# FTDI.net
KiCad netlist of a schematic drawn in Altium Designer
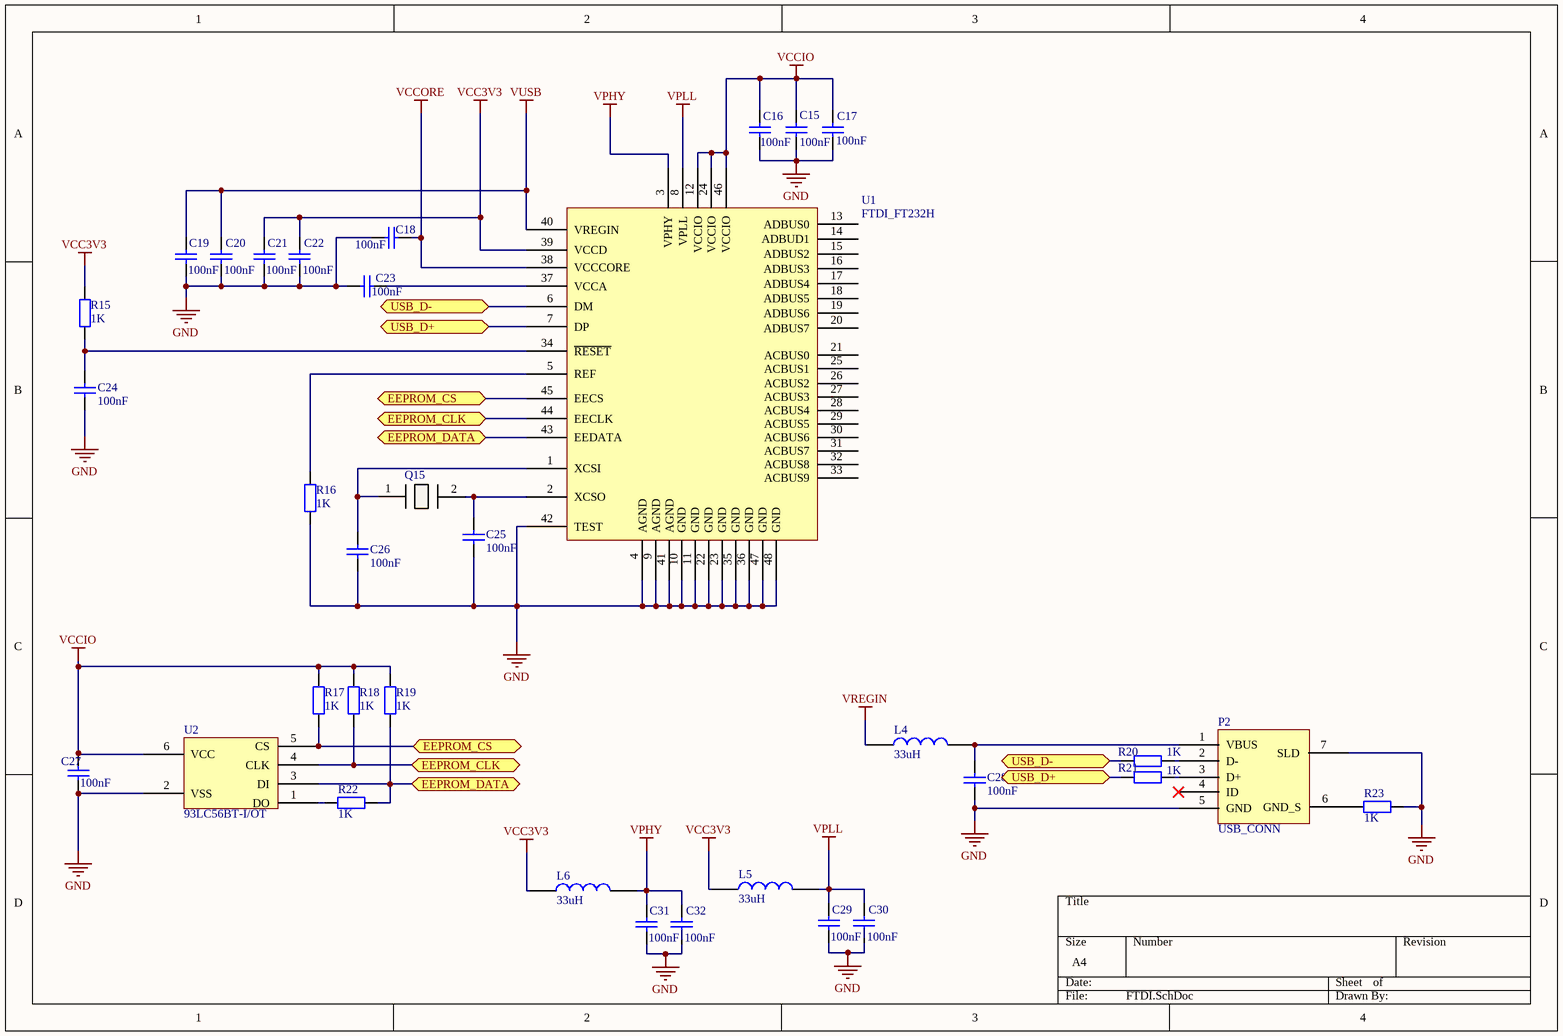
[diagram p0: FTDI.SchDoc]

(export (version "E")
  (design (tool "Eeschema 10.0.6"))
  (components
    (comp (ref "C15")
      (value "100nF")
      (footprint "AXIAL-0.3")
      (description "Capacitor")
      (libsource (lib "hallglib") (part "CAP"))
    )
    (comp (ref "C16")
      (value "100nF")
      (footprint "AXIAL-0.3")
      (description "Capacitor")
      (libsource (lib "hallglib") (part "CAP"))
    )
    (comp (ref "C17")
      (value "100nF")
      (footprint "AXIAL-0.3")
      (description "Capacitor")
      (libsource (lib "hallglib") (part "CAP"))
    )
    (comp (ref "C18")
      (value "100nF")
      (footprint "AXIAL-0.3")
      (description "Capacitor")
      (libsource (lib "hallglib") (part "CAP"))
    )
    (comp (ref "C19")
      (value "100nF")
      (footprint "AXIAL-0.3")
      (description "Capacitor")
      (libsource (lib "hallglib") (part "CAP"))
    )
    (comp (ref "C20")
      (value "100nF")
      (footprint "AXIAL-0.3")
      (description "Capacitor")
      (libsource (lib "hallglib") (part "CAP"))
    )
    (comp (ref "C21")
      (value "100nF")
      (footprint "AXIAL-0.3")
      (description "Capacitor")
      (libsource (lib "hallglib") (part "CAP"))
    )
    (comp (ref "C22")
      (value "100nF")
      (footprint "AXIAL-0.3")
      (description "Capacitor")
      (libsource (lib "hallglib") (part "CAP"))
    )
    (comp (ref "C23")
      (value "100nF")
      (footprint "AXIAL-0.3")
      (description "Capacitor")
      (libsource (lib "hallglib") (part "CAP"))
    )
    (comp (ref "C24")
      (value "100nF")
      (footprint "AXIAL-0.3")
      (description "Capacitor")
      (libsource (lib "hallglib") (part "CAP"))
    )
    (comp (ref "C25")
      (value "100nF")
      (footprint "AXIAL-0.3")
      (description "Capacitor")
      (libsource (lib "hallglib") (part "CAP"))
    )
    (comp (ref "C26")
      (value "100nF")
      (footprint "AXIAL-0.3")
      (description "Capacitor")
      (libsource (lib "hallglib") (part "CAP"))
    )
    (comp (ref "C27")
      (value "100nF")
      (footprint "AXIAL-0.3")
      (description "Capacitor")
      (libsource (lib "hallglib") (part "CAP"))
    )
    (comp (ref "C28")
      (value "100nF")
      (footprint "AXIAL-0.3")
      (description "Capacitor")
      (libsource (lib "hallglib") (part "CAP"))
    )
    (comp (ref "C29")
      (value "100nF")
      (footprint "AXIAL-0.3")
      (description "Capacitor")
      (libsource (lib "hallglib") (part "CAP"))
    )
    (comp (ref "C30")
      (value "100nF")
      (footprint "AXIAL-0.3")
      (description "Capacitor")
      (libsource (lib "hallglib") (part "CAP"))
    )
    (comp (ref "C31")
      (value "100nF")
      (footprint "AXIAL-0.3")
      (description "Capacitor")
      (libsource (lib "hallglib") (part "CAP"))
    )
    (comp (ref "C32")
      (value "100nF")
      (footprint "AXIAL-0.3")
      (description "Capacitor")
      (libsource (lib "hallglib") (part "CAP"))
    )
    (comp (ref "L4")
      (value "33uH")
      (footprint "AXIAL-0.3")
      (description "Inductor")
      (libsource (lib "hallglib") (part "IND"))
    )
    (comp (ref "L5")
      (value "33uH")
      (footprint "AXIAL-0.3")
      (description "Inductor")
      (libsource (lib "hallglib") (part "IND"))
    )
    (comp (ref "L6")
      (value "33uH")
      (footprint "AXIAL-0.3")
      (description "Inductor")
      (libsource (lib "hallglib") (part "IND"))
    )
    (comp (ref "P2")
      (value "USB_CONN")
      (footprint "SMD_Micro_USB")
      (description "usb, smd csatlakozó")
      (libsource (lib "hallglib") (part "USB_connector"))
    )
    (comp (ref "Q15")
      (value "HC49/4HSMX")
      (footprint "Crystal_10MHz")
      (description "kristály")
      (libsource (lib "hallglib") (part "HC49/4HSMX"))
    )
    (comp (ref "R15")
      (value "1K")
      (footprint "AXIAL-0.3")
      (description "Resistor")
      (libsource (lib "hallglib") (part "RES"))
    )
    (comp (ref "R16")
      (value "1K")
      (footprint "AXIAL-0.3")
      (description "Resistor")
      (libsource (lib "") (part "RES_1"))
    )
    (comp (ref "R17")
      (value "1K")
      (footprint "AXIAL-0.3")
      (description "Resistor")
      (libsource (lib "") (part "RES_1"))
    )
    (comp (ref "R18")
      (value "1K")
      (footprint "AXIAL-0.3")
      (description "Resistor")
      (libsource (lib "") (part "RES_1"))
    )
    (comp (ref "R19")
      (value "1K")
      (footprint "AXIAL-0.3")
      (description "Resistor")
      (libsource (lib "") (part "RES_1"))
    )
    (comp (ref "R20")
      (value "1K")
      (footprint "AXIAL-0.3")
      (description "Resistor")
      (libsource (lib "hallglib") (part "RES"))
    )
    (comp (ref "R21")
      (value "1K")
      (footprint "AXIAL-0.3")
      (description "Resistor")
      (libsource (lib "hallglib") (part "RES"))
    )
    (comp (ref "R22")
      (value "1K")
      (footprint "AXIAL-0.3")
      (description "Resistor")
      (libsource (lib "hallglib") (part "RES"))
    )
    (comp (ref "R23")
      (value "1K")
      (footprint "AXIAL-0.3")
      (description "Resistor")
      (libsource (lib "hallglib") (part "RES"))
    )
    (comp (ref "U1")
      (value "FTDI_FT232H")
      (footprint "LQFP48")
      (description "USB transciever")
      (libsource (lib "hallglib") (part "FTDI_FT232H"))
    )
    (comp (ref "U2")
      (value "93LC56BT-I/OT")
      (footprint "SOT-23")
      (description "EEPROM")
      (libsource (lib "hallglib") (part "93LC56BT-I/OT"))
    )
  )
  (nets
    (net (code "1") (name "/EEPROM_CLK") (class "Default")
      (node (ref "R18") (pin "1") (pinfunction "1_1") (pintype "passive"))
      (node (ref "U1") (pin "44") (pinfunction "EECLK_44") (pintype "passive"))
      (node (ref "U2") (pin "4") (pinfunction "CLK_4") (pintype "passive"))
    )
    (net (code "2") (name "/EEPROM_CS") (class "Default")
      (node (ref "R17") (pin "1") (pinfunction "1_1") (pintype "passive"))
      (node (ref "U1") (pin "45") (pinfunction "EECS_45") (pintype "passive"))
      (node (ref "U2") (pin "5") (pinfunction "CS_5") (pintype "passive"))
    )
    (net (code "3") (name "/EEPROM_DATA") (class "Default")
      (node (ref "R19") (pin "1") (pinfunction "1_1") (pintype "passive"))
      (node (ref "R22") (pin "2") (pinfunction "2_2") (pintype "passive"))
      (node (ref "U1") (pin "43") (pinfunction "EEDATA_43") (pintype "passive"))
      (node (ref "U2") (pin "3") (pinfunction "DI_3") (pintype "passive"))
    )
    (net (code "4") (name "/USB_D+") (class "Default")
      (node (ref "R21") (pin "1") (pinfunction "1_1") (pintype "passive"))
      (node (ref "U1") (pin "7") (pinfunction "DP_7") (pintype "passive"))
    )
    (net (code "5") (name "/USB_D-") (class "Default")
      (node (ref "R20") (pin "1") (pinfunction "1_1") (pintype "passive"))
      (node (ref "U1") (pin "6") (pinfunction "DM_6") (pintype "passive"))
    )
    (net (code "6") (name "GND") (class "Default")
      (node (ref "C15") (pin "1") (pinfunction "1_1") (pintype "passive"))
      (node (ref "C16") (pin "1") (pinfunction "1_1") (pintype "passive"))
      (node (ref "C17") (pin "1") (pinfunction "1_1") (pintype "passive"))
      (node (ref "C18") (pin "1") (pinfunction "1_1") (pintype "passive"))
      (node (ref "C19") (pin "1") (pinfunction "1_1") (pintype "passive"))
      (node (ref "C20") (pin "1") (pinfunction "1_1") (pintype "passive"))
      (node (ref "C21") (pin "1") (pinfunction "1_1") (pintype "passive"))
      (node (ref "C22") (pin "1") (pinfunction "1_1") (pintype "passive"))
      (node (ref "C23") (pin "2") (pinfunction "2_2") (pintype "passive"))
      (node (ref "C24") (pin "1") (pinfunction "1_1") (pintype "passive"))
      (node (ref "C25") (pin "1") (pinfunction "1_1") (pintype "passive"))
      (node (ref "C26") (pin "1") (pinfunction "1_1") (pintype "passive"))
      (node (ref "C27") (pin "1") (pinfunction "1_1") (pintype "passive"))
      (node (ref "C28") (pin "1") (pinfunction "1_1") (pintype "passive"))
      (node (ref "C29") (pin "1") (pinfunction "1_1") (pintype "passive"))
      (node (ref "C30") (pin "1") (pinfunction "1_1") (pintype "passive"))
      (node (ref "C31") (pin "1") (pinfunction "1_1") (pintype "passive"))
      (node (ref "C32") (pin "1") (pinfunction "1_1") (pintype "passive"))
      (node (ref "P2") (pin "5") (pinfunction "GND_5") (pintype "passive"))
      (node (ref "P2") (pin "7") (pinfunction "SLD_7") (pintype "passive"))
      (node (ref "R16") (pin "1") (pinfunction "1_1") (pintype "passive"))
      (node (ref "R23") (pin "2") (pinfunction "2_2") (pintype "passive"))
      (node (ref "U1") (pin "10") (pinfunction "GND_10") (pintype "passive"))
      (node (ref "U1") (pin "11") (pinfunction "GND_11") (pintype "passive"))
      (node (ref "U1") (pin "22") (pinfunction "GND_22") (pintype "passive"))
      (node (ref "U1") (pin "23") (pinfunction "GND_23") (pintype "passive"))
      (node (ref "U1") (pin "35") (pinfunction "GND_35") (pintype "passive"))
      (node (ref "U1") (pin "36") (pinfunction "GND_36") (pintype "passive"))
      (node (ref "U1") (pin "4") (pinfunction "AGND_4") (pintype "passive"))
      (node (ref "U1") (pin "41") (pinfunction "AGND_41") (pintype "passive"))
      (node (ref "U1") (pin "42") (pinfunction "TEST_42") (pintype "passive"))
      (node (ref "U1") (pin "47") (pinfunction "GND_47") (pintype "passive"))
      (node (ref "U1") (pin "48") (pinfunction "GND_48") (pintype "passive"))
      (node (ref "U1") (pin "9") (pinfunction "AGND_9") (pintype "passive"))
      (node (ref "U2") (pin "2") (pinfunction "VSS_2") (pintype "passive"))
    )
    (net (code "7") (name "Net-(P2-D+)") (class "Default")
      (node (ref "P2") (pin "3") (pinfunction "D+_3") (pintype "passive"))
      (node (ref "R21") (pin "2") (pinfunction "2_2") (pintype "passive"))
    )
    (net (code "8") (name "Net-(P2-D-)") (class "Default")
      (node (ref "P2") (pin "2") (pinfunction "D-_2") (pintype "passive"))
      (node (ref "R20") (pin "2") (pinfunction "2_2") (pintype "passive"))
    )
    (net (code "9") (name "Net-(P2-GND_S)") (class "Default")
      (node (ref "P2") (pin "6") (pinfunction "GND_S_6") (pintype "passive"))
      (node (ref "R23") (pin "1") (pinfunction "1_1") (pintype "passive"))
    )
    (net (code "10") (name "Net-(P2-VBUS)") (class "Default")
      (node (ref "C28") (pin "2") (pinfunction "2_2") (pintype "passive"))
      (node (ref "L4") (pin "2") (pinfunction "2_2") (pintype "passive"))
      (node (ref "P2") (pin "1") (pinfunction "VBUS_1") (pintype "passive"))
    )
    (net (code "11") (name "Net-(Q15-X1)") (class "Default")
      (node (ref "C26") (pin "2") (pinfunction "2_2") (pintype "passive"))
      (node (ref "Q15") (pin "1") (pinfunction "X1_1") (pintype "passive"))
      (node (ref "U1") (pin "1") (pinfunction "XCSI_1") (pintype "passive"))
    )
    (net (code "12") (name "Net-(Q15-X2)") (class "Default")
      (node (ref "C25") (pin "2") (pinfunction "2_2") (pintype "passive"))
      (node (ref "Q15") (pin "2") (pinfunction "X2_2") (pintype "passive"))
      (node (ref "U1") (pin "2") (pinfunction "XCSO_2") (pintype "passive"))
    )
    (net (code "13") (name "Net-(U1-REF)") (class "Default")
      (node (ref "R16") (pin "2") (pinfunction "2_2") (pintype "passive"))
      (node (ref "U1") (pin "5") (pinfunction "REF_5") (pintype "passive"))
    )
    (net (code "14") (name "Net-(U1-VCCA)") (class "Default")
      (node (ref "C23") (pin "1") (pinfunction "1_1") (pintype "passive"))
      (node (ref "U1") (pin "37") (pinfunction "VCCA_37") (pintype "passive"))
    )
    (net (code "15") (name "Net-(U1-~{RESET})") (class "Default")
      (node (ref "C24") (pin "2") (pinfunction "2_2") (pintype "passive"))
      (node (ref "R15") (pin "1") (pinfunction "1_1") (pintype "passive"))
      (node (ref "U1") (pin "34") (pinfunction "~{RESET}_34") (pintype "passive"))
    )
    (net (code "16") (name "Net-(U2-DO)") (class "Default")
      (node (ref "R22") (pin "1") (pinfunction "1_1") (pintype "passive"))
      (node (ref "U2") (pin "1") (pinfunction "DO_1") (pintype "passive"))
    )
    (net (code "17") (name "VCC3V3") (class "Default")
      (node (ref "C21") (pin "2") (pinfunction "2_2") (pintype "passive"))
      (node (ref "C22") (pin "2") (pinfunction "2_2") (pintype "passive"))
      (node (ref "L5") (pin "1") (pinfunction "1_1") (pintype "passive"))
      (node (ref "L6") (pin "1") (pinfunction "1_1") (pintype "passive"))
      (node (ref "R15") (pin "2") (pinfunction "2_2") (pintype "passive"))
      (node (ref "U1") (pin "39") (pinfunction "VCCD_39") (pintype "passive"))
    )
    (net (code "18") (name "VCCIO") (class "Default")
      (node (ref "C15") (pin "2") (pinfunction "2_2") (pintype "passive"))
      (node (ref "C16") (pin "2") (pinfunction "2_2") (pintype "passive"))
      (node (ref "C17") (pin "2") (pinfunction "2_2") (pintype "passive"))
      (node (ref "C27") (pin "2") (pinfunction "2_2") (pintype "passive"))
      (node (ref "R17") (pin "2") (pinfunction "2_2") (pintype "passive"))
      (node (ref "R18") (pin "2") (pinfunction "2_2") (pintype "passive"))
      (node (ref "R19") (pin "2") (pinfunction "2_2") (pintype "passive"))
      (node (ref "U1") (pin "12") (pinfunction "VCCIO_12") (pintype "passive"))
      (node (ref "U1") (pin "24") (pinfunction "VCCIO_24") (pintype "passive"))
      (node (ref "U1") (pin "46") (pinfunction "VCCIO_46") (pintype "passive"))
      (node (ref "U2") (pin "6") (pinfunction "VCC_6") (pintype "passive"))
    )
    (net (code "19") (name "VCCORE") (class "Default")
      (node (ref "C18") (pin "2") (pinfunction "2_2") (pintype "passive"))
      (node (ref "U1") (pin "38") (pinfunction "VCCCORE_38") (pintype "passive"))
    )
    (net (code "20") (name "VPHY") (class "Default")
      (node (ref "C31") (pin "2") (pinfunction "2_2") (pintype "passive"))
      (node (ref "C32") (pin "2") (pinfunction "2_2") (pintype "passive"))
      (node (ref "L6") (pin "2") (pinfunction "2_2") (pintype "passive"))
      (node (ref "U1") (pin "3") (pinfunction "VPHY_3") (pintype "passive"))
    )
    (net (code "21") (name "VPLL") (class "Default")
      (node (ref "C29") (pin "2") (pinfunction "2_2") (pintype "passive"))
      (node (ref "C30") (pin "2") (pinfunction "2_2") (pintype "passive"))
      (node (ref "L5") (pin "2") (pinfunction "2_2") (pintype "passive"))
      (node (ref "U1") (pin "8") (pinfunction "VPLL_8") (pintype "passive"))
    )
    (net (code "22") (name "VREGIN") (class "Default")
      (node (ref "L4") (pin "1") (pinfunction "1_1") (pintype "passive"))
    )
    (net (code "23") (name "VUSB") (class "Default")
      (node (ref "C19") (pin "2") (pinfunction "2_2") (pintype "passive"))
      (node (ref "C20") (pin "2") (pinfunction "2_2") (pintype "passive"))
      (node (ref "U1") (pin "40") (pinfunction "VREGIN_40") (pintype "passive"))
    )
    (net (code "24") (name "unconnected-(P2-ID-Pad4)") (class "Default")
      (node (ref "P2") (pin "4") (pinfunction "ID_4") (pintype "passive+no_connect"))
    )
    (net (code "25") (name "unconnected-(U1-ACBUS0-Pad21)") (class "Default")
      (node (ref "U1") (pin "21") (pinfunction "ACBUS0_21") (pintype "passive"))
    )
    (net (code "26") (name "unconnected-(U1-ACBUS1-Pad25)") (class "Default")
      (node (ref "U1") (pin "25") (pinfunction "ACBUS1_25") (pintype "passive"))
    )
    (net (code "27") (name "unconnected-(U1-ACBUS2-Pad26)") (class "Default")
      (node (ref "U1") (pin "26") (pinfunction "ACBUS2_26") (pintype "passive"))
    )
    (net (code "28") (name "unconnected-(U1-ACBUS3-Pad27)") (class "Default")
      (node (ref "U1") (pin "27") (pinfunction "ACBUS3_27") (pintype "passive"))
    )
    (net (code "29") (name "unconnected-(U1-ACBUS4-Pad28)") (class "Default")
      (node (ref "U1") (pin "28") (pinfunction "ACBUS4_28") (pintype "passive"))
    )
    (net (code "30") (name "unconnected-(U1-ACBUS5-Pad29)") (class "Default")
      (node (ref "U1") (pin "29") (pinfunction "ACBUS5_29") (pintype "passive"))
    )
    (net (code "31") (name "unconnected-(U1-ACBUS6-Pad30)") (class "Default")
      (node (ref "U1") (pin "30") (pinfunction "ACBUS6_30") (pintype "passive"))
    )
    (net (code "32") (name "unconnected-(U1-ACBUS7-Pad31)") (class "Default")
      (node (ref "U1") (pin "31") (pinfunction "ACBUS7_31") (pintype "passive"))
    )
    (net (code "33") (name "unconnected-(U1-ACBUS8-Pad32)") (class "Default")
      (node (ref "U1") (pin "32") (pinfunction "ACBUS8_32") (pintype "passive"))
    )
    (net (code "34") (name "unconnected-(U1-ACBUS9-Pad33)") (class "Default")
      (node (ref "U1") (pin "33") (pinfunction "ACBUS9_33") (pintype "passive"))
    )
    (net (code "35") (name "unconnected-(U1-ADBUD1-Pad14)") (class "Default")
      (node (ref "U1") (pin "14") (pinfunction "ADBUD1_14") (pintype "passive"))
    )
    (net (code "36") (name "unconnected-(U1-ADBUS0-Pad13)") (class "Default")
      (node (ref "U1") (pin "13") (pinfunction "ADBUS0_13") (pintype "passive"))
    )
    (net (code "37") (name "unconnected-(U1-ADBUS2-Pad15)") (class "Default")
      (node (ref "U1") (pin "15") (pinfunction "ADBUS2_15") (pintype "passive"))
    )
    (net (code "38") (name "unconnected-(U1-ADBUS3-Pad16)") (class "Default")
      (node (ref "U1") (pin "16") (pinfunction "ADBUS3_16") (pintype "passive"))
    )
    (net (code "39") (name "unconnected-(U1-ADBUS4-Pad17)") (class "Default")
      (node (ref "U1") (pin "17") (pinfunction "ADBUS4_17") (pintype "passive"))
    )
    (net (code "40") (name "unconnected-(U1-ADBUS5-Pad18)") (class "Default")
      (node (ref "U1") (pin "18") (pinfunction "ADBUS5_18") (pintype "passive"))
    )
    (net (code "41") (name "unconnected-(U1-ADBUS6-Pad19)") (class "Default")
      (node (ref "U1") (pin "19") (pinfunction "ADBUS6_19") (pintype "passive"))
    )
    (net (code "42") (name "unconnected-(U1-ADBUS7-Pad20)") (class "Default")
      (node (ref "U1") (pin "20") (pinfunction "ADBUS7_20") (pintype "passive"))
    )
  )
)
